# 02-MCU.net
KiCad netlist of a schematic drawn in Altium Designer
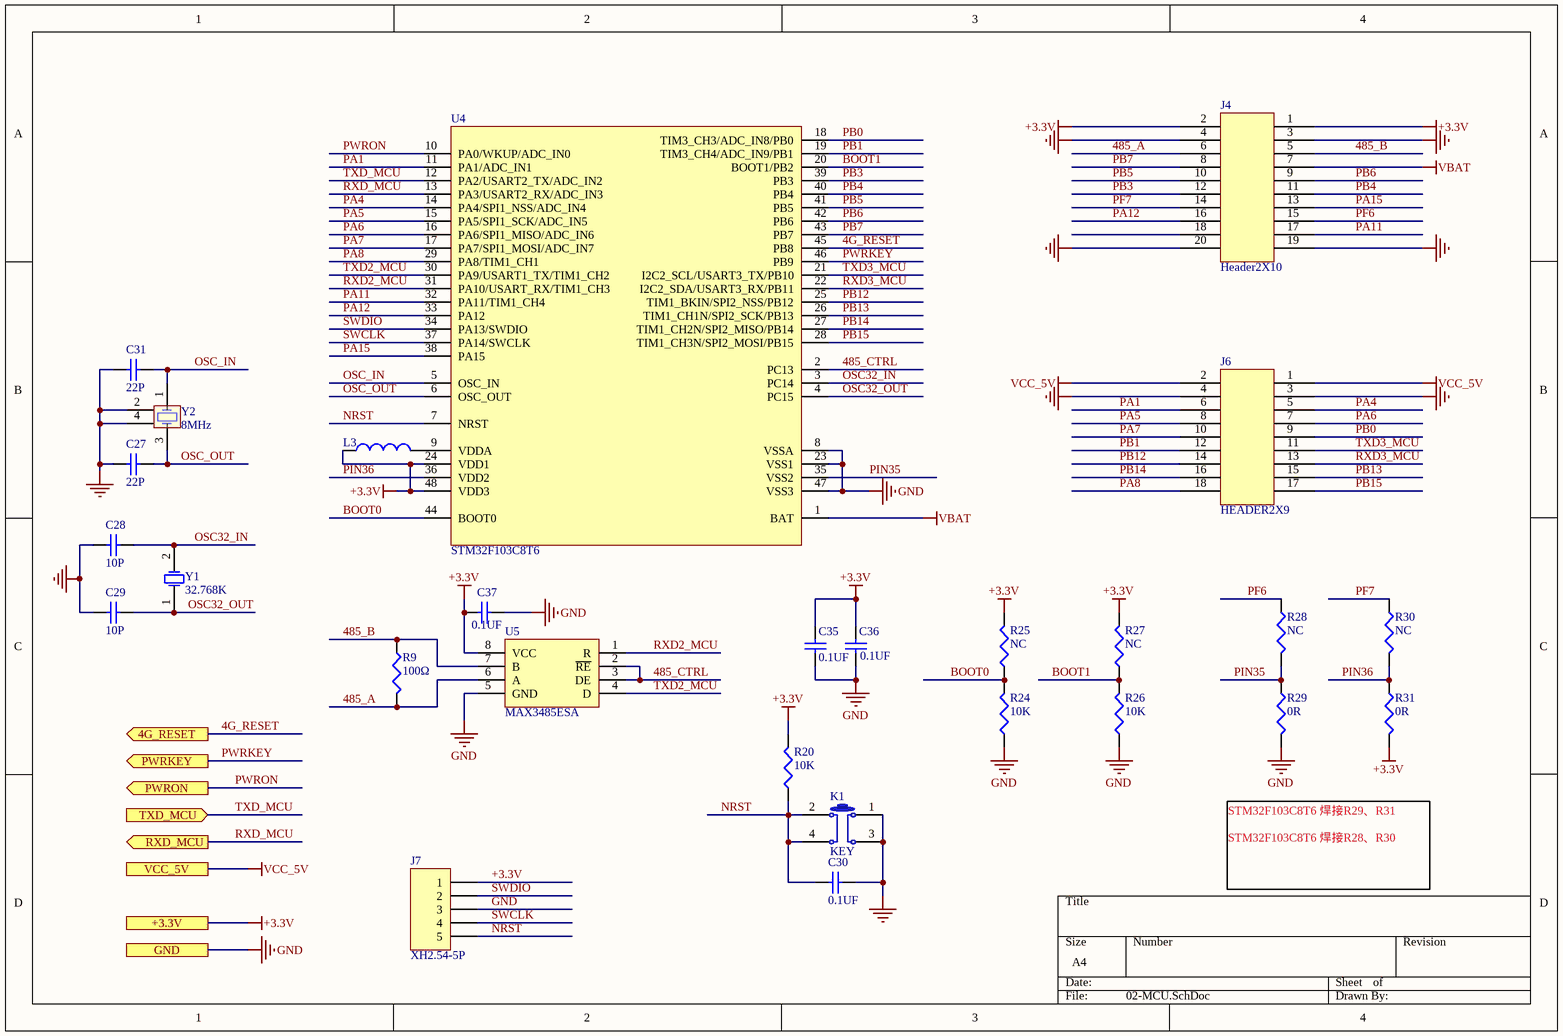
[diagram p0: 02-MCU.SchDoc]

(export (version "E")
  (design (tool "Eeschema 10.0.6"))
  (components
    (comp (ref "C27")
      (value "22P")
      (footprint "0603_C")
      (description "Capacitor")
      (fields (field (name "Comment") "Cap") (field (name "PUBLISHER") "Altium Limited"))
      (libsource (lib "Miscellaneous Devices") (part "Cap"))
    )
    (comp (ref "C28")
      (value "10P")
      (footprint "0603_C")
      (description "Capacitor")
      (fields (field (name "Comment") "Cap") (field (name "PUBLISHER") "Altium Limited"))
      (libsource (lib "Miscellaneous Devices") (part "Cap"))
    )
    (comp (ref "C29")
      (value "10P")
      (footprint "0603_C")
      (description "Capacitor")
      (fields (field (name "Comment") "Cap") (field (name "PUBLISHER") "Altium Limited"))
      (libsource (lib "Miscellaneous Devices") (part "Cap"))
    )
    (comp (ref "C30")
      (value "0.1UF")
      (footprint "0603_C")
      (description "Capacitor")
      (fields (field (name "Comment") "Cap") (field (name "PUBLISHER") "Altium Limited"))
      (libsource (lib "Miscellaneous Devices") (part "Cap"))
    )
    (comp (ref "C31")
      (value "22P")
      (footprint "0603_C")
      (description "Capacitor")
      (fields (field (name "Comment") "Cap") (field (name "PUBLISHER") "Altium Limited"))
      (libsource (lib "Miscellaneous Devices") (part "Cap"))
    )
    (comp (ref "C35")
      (value "0.1UF")
      (footprint "0603_C")
      (description "Capacitor")
      (fields (field (name "Comment") "Cap") (field (name "PUBLISHER") "Altium Limited"))
      (libsource (lib "Miscellaneous Devices") (part "Cap"))
    )
    (comp (ref "C36")
      (value "0.1UF")
      (footprint "0603_C")
      (description "Capacitor")
      (fields (field (name "Comment") "Cap") (field (name "PUBLISHER") "Altium Limited"))
      (libsource (lib "Miscellaneous Devices") (part "Cap"))
    )
    (comp (ref "C37")
      (value "0.1UF")
      (footprint "0603_C")
      (description "Capacitor")
      (fields (field (name "Comment") "Cap") (field (name "PUBLISHER") "Altium Limited"))
      (libsource (lib "Miscellaneous Devices") (part "Cap"))
    )
    (comp (ref "J4")
      (value "Header2X10")
      (footprint "DIP20-2.54-2.54")
      (libsource (lib "MySchlib") (part "Header2X10"))
    )
    (comp (ref "J6")
      (value "HEADER2X9")
      (footprint "DIP18-2.54-2.54")
      (libsource (lib "MySchlib") (part "HEADER2X9"))
    )
    (comp (ref "J7")
      (value "XH2.54-5P")
      (footprint "SIP5")
      (description "Header, 5-Pin, Right Angle")
      (fields (field (name "PUBLISHER") "Altium Limited"))
      (libsource (lib "Miscellaneous Connectors") (part "Header 5H"))
    )
    (comp (ref "K1") (value "KEY") (footprint "KEY_SMD5465") (libsource (lib "Schlib1") (part "KEY")))
    (comp (ref "L3")
      (value "Inductor")
      (footprint "0603_R")
      (fields (field (name "PUBLISHER") "Altium Limited"))
      (libsource (lib "Miscellaneous Devices") (part "Inductor"))
    )
    (comp (ref "R9") (value "100Ω") (footprint "0603_R") (libsource (lib "MySchlib") (part "RES1")))
    (comp (ref "R20")
      (value "10K")
      (footprint "0603_R")
      (description "Resistor")
      (fields (field (name "Comment") "Res3") (field (name "PUBLISHER") "Altium Limited"))
      (libsource (lib "Miscellaneous Devices") (part "Res3"))
    )
    (comp (ref "R24")
      (value "10K")
      (footprint "0603_R")
      (description "Resistor")
      (fields (field (name "Comment") "Res3") (field (name "PUBLISHER") "Altium Limited"))
      (libsource (lib "Miscellaneous Devices") (part "Res3"))
    )
    (comp (ref "R25")
      (value "NC")
      (footprint "0603_R")
      (description "Resistor")
      (fields (field (name "Comment") "Res3") (field (name "PUBLISHER") "Altium Limited"))
      (libsource (lib "Miscellaneous Devices") (part "Res3"))
    )
    (comp (ref "R26")
      (value "10K")
      (footprint "0603_R")
      (description "Resistor")
      (fields (field (name "Comment") "Res3") (field (name "PUBLISHER") "Altium Limited"))
      (libsource (lib "Miscellaneous Devices") (part "Res3"))
    )
    (comp (ref "R27")
      (value "NC")
      (footprint "0603_R")
      (description "Resistor")
      (fields (field (name "Comment") "Res3") (field (name "PUBLISHER") "Altium Limited"))
      (libsource (lib "Miscellaneous Devices") (part "Res3"))
    )
    (comp (ref "R28")
      (value "NC")
      (footprint "0603_R")
      (description "Resistor")
      (fields (field (name "Comment") "Res3") (field (name "PUBLISHER") "Altium Limited"))
      (libsource (lib "Miscellaneous Devices") (part "Res3"))
    )
    (comp (ref "R29")
      (value "0R")
      (footprint "0603_R")
      (description "Resistor")
      (fields (field (name "Comment") "Res3") (field (name "PUBLISHER") "Altium Limited"))
      (libsource (lib "Miscellaneous Devices") (part "Res3"))
    )
    (comp (ref "R30")
      (value "NC")
      (footprint "0603_R")
      (description "Resistor")
      (fields (field (name "Comment") "Res3") (field (name "PUBLISHER") "Altium Limited"))
      (libsource (lib "Miscellaneous Devices") (part "Res3"))
    )
    (comp (ref "R31")
      (value "0R")
      (footprint "0603_R")
      (description "Resistor")
      (fields (field (name "Comment") "Res3") (field (name "PUBLISHER") "Altium Limited"))
      (libsource (lib "Miscellaneous Devices") (part "Res3"))
    )
    (comp (ref "U4")
      (value "STM32F103C8T6")
      (footprint "LQFP48")
      (libsource (lib "MySchlib") (part "STM32F103C8T6"))
    )
    (comp (ref "U5") (value "MAX3485ESA") (footprint "SO8") (libsource (lib "MySchlib") (part "MAX485")))
    (comp (ref "Y1")
      (value "32.768K")
      (footprint "3215")
      (description "Crystal Oscillator")
      (fields (field (name "PUBLISHER") "Altium Limited"))
      (libsource (lib "Miscellaneous Devices") (part "XTAL"))
    )
    (comp (ref "Y2")
      (value "8MHz")
      (footprint "CRY_S3225")
      (description "CRYSTAL_S4_PASSIVE")
      (libsource (lib "EP_MCB_V4.1") (part "CRYSTAL_S4_1"))
    )
  )
  (nets
    (net (code "1") (name "+3.3V") (class "Default")
      (node (ref "C35") (pin "1") (pinfunction "1_1") (pintype "passive"))
      (node (ref "C36") (pin "1") (pinfunction "1_1") (pintype "passive"))
      (node (ref "C37") (pin "1") (pinfunction "1_1") (pintype "passive"))
      (node (ref "J4") (pin "1") (pinfunction "1_1") (pintype "passive"))
      (node (ref "J4") (pin "2") (pinfunction "2_2") (pintype "passive"))
      (node (ref "J7") (pin "1") (pinfunction "1_1") (pintype "passive"))
      (node (ref "L3") (pin "1") (pinfunction "1_1") (pintype "passive"))
      (node (ref "R20") (pin "2") (pinfunction "2_2") (pintype "passive"))
      (node (ref "R25") (pin "2") (pinfunction "2_2") (pintype "passive"))
      (node (ref "R27") (pin "2") (pinfunction "2_2") (pintype "passive"))
      (node (ref "R31") (pin "2") (pinfunction "2_2") (pintype "passive"))
      (node (ref "U4") (pin "24") (pinfunction "VDD1_24") (pintype "passive"))
      (node (ref "U4") (pin "48") (pinfunction "VDD3_48") (pintype "passive"))
      (node (ref "U5") (pin "8") (pinfunction "VCC_8") (pintype "passive"))
    )
    (net (code "2") (name "/4G_RESET") (class "Default")
      (node (ref "U4") (pin "45") (pinfunction "PB8_45") (pintype "passive"))
    )
    (net (code "3") (name "/485_A") (class "Default")
      (node (ref "J4") (pin "6") (pinfunction "6_6") (pintype "passive"))
      (node (ref "R9") (pin "2") (pinfunction "2_2") (pintype "passive"))
      (node (ref "U5") (pin "6") (pinfunction "A_6") (pintype "passive"))
    )
    (net (code "4") (name "/485_B") (class "Default")
      (node (ref "J4") (pin "5") (pinfunction "5_5") (pintype "passive"))
      (node (ref "R9") (pin "1") (pinfunction "1_1") (pintype "passive"))
      (node (ref "U5") (pin "7") (pinfunction "B_7") (pintype "passive"))
    )
    (net (code "5") (name "/485_CTRL") (class "Default")
      (node (ref "U4") (pin "2") (pinfunction "PC13_2") (pintype "passive"))
      (node (ref "U5") (pin "2") (pinfunction "~{RE}_2") (pintype "passive"))
      (node (ref "U5") (pin "3") (pinfunction "DE_3") (pintype "passive"))
    )
    (net (code "6") (name "/BOOT0") (class "Default")
      (node (ref "R24") (pin "2") (pinfunction "2_2") (pintype "passive"))
      (node (ref "R25") (pin "1") (pinfunction "1_1") (pintype "passive"))
      (node (ref "U4") (pin "44") (pinfunction "BOOT0_44") (pintype "passive"))
    )
    (net (code "7") (name "/BOOT1") (class "Default")
      (node (ref "R26") (pin "2") (pinfunction "2_2") (pintype "passive"))
      (node (ref "R27") (pin "1") (pinfunction "1_1") (pintype "passive"))
      (node (ref "U4") (pin "20") (pinfunction "BOOT1/PB2_20") (pintype "passive"))
    )
    (net (code "8") (name "/NRST") (class "Default")
      (node (ref "C30") (pin "2") (pinfunction "2_2") (pintype "passive"))
      (node (ref "J7") (pin "5") (pinfunction "5_5") (pintype "passive"))
      (node (ref "K1") (pin "2") (pinfunction "2_2") (pintype "passive"))
      (node (ref "K1") (pin "4") (pinfunction "4_4") (pintype "passive"))
      (node (ref "R20") (pin "1") (pinfunction "1_1") (pintype "passive"))
      (node (ref "U4") (pin "7") (pinfunction "NRST_7") (pintype "passive"))
    )
    (net (code "9") (name "/OSC32_IN") (class "Default")
      (node (ref "C28") (pin "1") (pinfunction "1_1") (pintype "passive"))
      (node (ref "U4") (pin "3") (pinfunction "PC14_3") (pintype "passive"))
      (node (ref "Y1") (pin "2") (pinfunction "OSC2_2") (pintype "passive"))
    )
    (net (code "10") (name "/OSC32_OUT") (class "Default")
      (node (ref "C29") (pin "1") (pinfunction "1_1") (pintype "passive"))
      (node (ref "U4") (pin "4") (pinfunction "PC15_4") (pintype "passive"))
      (node (ref "Y1") (pin "1") (pinfunction "OSC1_1") (pintype "passive"))
    )
    (net (code "11") (name "/OSC_IN") (class "Default")
      (node (ref "C31") (pin "1") (pinfunction "1_1") (pintype "passive"))
      (node (ref "U4") (pin "5") (pinfunction "OSC_IN_5") (pintype "passive"))
      (node (ref "Y2") (pin "1") (pinfunction "1_1") (pintype "passive"))
    )
    (net (code "12") (name "/OSC_OUT") (class "Default")
      (node (ref "C27") (pin "1") (pinfunction "1_1") (pintype "passive"))
      (node (ref "U4") (pin "6") (pinfunction "OSC_OUT_6") (pintype "passive"))
      (node (ref "Y2") (pin "3") (pinfunction "3_3") (pintype "passive"))
    )
    (net (code "13") (name "/PA1") (class "Default")
      (node (ref "J6") (pin "6") (pinfunction "6_6") (pintype "passive"))
      (node (ref "U4") (pin "11") (pinfunction "PA1/ADC_IN1_11") (pintype "passive"))
    )
    (net (code "14") (name "/PA4") (class "Default")
      (node (ref "J6") (pin "5") (pinfunction "5_5") (pintype "passive"))
      (node (ref "U4") (pin "14") (pinfunction "PA4/SPI1_NSS/ADC_IN4_14") (pintype "passive"))
    )
    (net (code "15") (name "/PA5") (class "Default")
      (node (ref "J6") (pin "8") (pinfunction "8_8") (pintype "passive"))
      (node (ref "U4") (pin "15") (pinfunction "PA5/SPI1_SCK/ADC_IN5_15") (pintype "passive"))
    )
    (net (code "16") (name "/PA6") (class "Default")
      (node (ref "J6") (pin "7") (pinfunction "7_7") (pintype "passive"))
      (node (ref "U4") (pin "16") (pinfunction "PA6/SPI1_MISO/ADC_IN6_16") (pintype "passive"))
    )
    (net (code "17") (name "/PA7") (class "Default")
      (node (ref "J6") (pin "10") (pinfunction "10_10") (pintype "passive"))
      (node (ref "U4") (pin "17") (pinfunction "PA7/SPI1_MOSI/ADC_IN7_17") (pintype "passive"))
    )
    (net (code "18") (name "/PA8") (class "Default")
      (node (ref "J6") (pin "18") (pinfunction "18_18") (pintype "passive"))
      (node (ref "U4") (pin "29") (pinfunction "PA8/TIM1_CH1_29") (pintype "passive"))
    )
    (net (code "19") (name "/PA11") (class "Default")
      (node (ref "J4") (pin "17") (pinfunction "17_17") (pintype "passive"))
      (node (ref "U4") (pin "32") (pinfunction "PA11/TIM1_CH4_32") (pintype "passive"))
    )
    (net (code "20") (name "/PA12") (class "Default")
      (node (ref "J4") (pin "16") (pinfunction "16_16") (pintype "passive"))
      (node (ref "U4") (pin "33") (pinfunction "PA12_33") (pintype "passive"))
    )
    (net (code "21") (name "/PA15") (class "Default")
      (node (ref "J4") (pin "13") (pinfunction "13_13") (pintype "passive"))
      (node (ref "U4") (pin "38") (pinfunction "PA15_38") (pintype "passive"))
    )
    (net (code "22") (name "/PB0") (class "Default")
      (node (ref "J6") (pin "9") (pinfunction "9_9") (pintype "passive"))
      (node (ref "U4") (pin "18") (pinfunction "TIM3_CH3/ADC_IN8/PB0_18") (pintype "passive"))
    )
    (net (code "23") (name "/PB1") (class "Default")
      (node (ref "J6") (pin "12") (pinfunction "12_12") (pintype "passive"))
      (node (ref "U4") (pin "19") (pinfunction "TIM3_CH4/ADC_IN9/PB1_19") (pintype "passive"))
    )
    (net (code "24") (name "/PB3") (class "Default")
      (node (ref "J4") (pin "12") (pinfunction "12_12") (pintype "passive"))
      (node (ref "U4") (pin "39") (pinfunction "PB3_39") (pintype "passive"))
    )
    (net (code "25") (name "/PB4") (class "Default")
      (node (ref "J4") (pin "11") (pinfunction "11_11") (pintype "passive"))
      (node (ref "U4") (pin "40") (pinfunction "PB4_40") (pintype "passive"))
    )
    (net (code "26") (name "/PB5") (class "Default")
      (node (ref "J4") (pin "10") (pinfunction "10_10") (pintype "passive"))
      (node (ref "U4") (pin "41") (pinfunction "PB5_41") (pintype "passive"))
    )
    (net (code "27") (name "/PB6") (class "Default")
      (node (ref "J4") (pin "9") (pinfunction "9_9") (pintype "passive"))
      (node (ref "U4") (pin "42") (pinfunction "PB6_42") (pintype "passive"))
    )
    (net (code "28") (name "/PB7") (class "Default")
      (node (ref "J4") (pin "8") (pinfunction "8_8") (pintype "passive"))
      (node (ref "U4") (pin "43") (pinfunction "PB7_43") (pintype "passive"))
    )
    (net (code "29") (name "/PB12") (class "Default")
      (node (ref "J6") (pin "14") (pinfunction "14_14") (pintype "passive"))
      (node (ref "U4") (pin "25") (pinfunction "TIM1_BKIN/SPI2_NSS/PB12_25") (pintype "passive"))
    )
    (net (code "30") (name "/PB13") (class "Default")
      (node (ref "J6") (pin "15") (pinfunction "15_15") (pintype "passive"))
      (node (ref "U4") (pin "26") (pinfunction "TIM1_CH1N/SPI2_SCK/PB13_26") (pintype "passive"))
    )
    (net (code "31") (name "/PB14") (class "Default")
      (node (ref "J6") (pin "16") (pinfunction "16_16") (pintype "passive"))
      (node (ref "U4") (pin "27") (pinfunction "TIM1_CH2N/SPI2_MISO/PB14_27") (pintype "passive"))
    )
    (net (code "32") (name "/PB15") (class "Default")
      (node (ref "J6") (pin "17") (pinfunction "17_17") (pintype "passive"))
      (node (ref "U4") (pin "28") (pinfunction "TIM1_CH3N/SPI2_MOSI/PB15_28") (pintype "passive"))
    )
    (net (code "33") (name "/PF6") (class "Default")
      (node (ref "J4") (pin "15") (pinfunction "15_15") (pintype "passive"))
      (node (ref "R28") (pin "1") (pinfunction "1_1") (pintype "passive"))
    )
    (net (code "34") (name "/PF7") (class "Default")
      (node (ref "J4") (pin "14") (pinfunction "14_14") (pintype "passive"))
      (node (ref "R30") (pin "1") (pinfunction "1_1") (pintype "passive"))
    )
    (net (code "35") (name "/PIN35") (class "Default")
      (node (ref "R28") (pin "2") (pinfunction "2_2") (pintype "passive"))
      (node (ref "R29") (pin "1") (pinfunction "1_1") (pintype "passive"))
      (node (ref "U4") (pin "35") (pinfunction "VSS2_35") (pintype "passive"))
    )
    (net (code "36") (name "/PIN36") (class "Default")
      (node (ref "R30") (pin "2") (pinfunction "2_2") (pintype "passive"))
      (node (ref "R31") (pin "1") (pinfunction "1_1") (pintype "passive"))
      (node (ref "U4") (pin "36") (pinfunction "VDD2_36") (pintype "passive"))
    )
    (net (code "37") (name "/PWRKEY") (class "Default")
      (node (ref "U4") (pin "46") (pinfunction "PB9_46") (pintype "passive"))
    )
    (net (code "38") (name "/PWRON") (class "Default")
      (node (ref "U4") (pin "10") (pinfunction "PA0/WKUP/ADC_IN0_10") (pintype "passive"))
    )
    (net (code "39") (name "/RXD2_MCU") (class "Default")
      (node (ref "U4") (pin "31") (pinfunction "PA10/USART_RX/TIM1_CH3_31") (pintype "passive"))
      (node (ref "U5") (pin "1") (pinfunction "R_1") (pintype "passive"))
    )
    (net (code "40") (name "/RXD3_MCU") (class "Default")
      (node (ref "J6") (pin "13") (pinfunction "13_13") (pintype "passive"))
      (node (ref "U4") (pin "22") (pinfunction "I2C2_SDA/USART3_RX/PB11_22") (pintype "passive"))
    )
    (net (code "41") (name "/RXD_MCU") (class "Default")
      (node (ref "U4") (pin "13") (pinfunction "PA3/USART2_RX/ADC_IN3_13") (pintype "passive"))
    )
    (net (code "42") (name "/SWCLK") (class "Default")
      (node (ref "J7") (pin "4") (pinfunction "4_4") (pintype "passive"))
      (node (ref "U4") (pin "37") (pinfunction "PA14/SWCLK_37") (pintype "passive"))
    )
    (net (code "43") (name "/SWDIO") (class "Default")
      (node (ref "J7") (pin "2") (pinfunction "2_2") (pintype "passive"))
      (node (ref "U4") (pin "34") (pinfunction "PA13/SWDIO_34") (pintype "passive"))
    )
    (net (code "44") (name "/TXD2_MCU") (class "Default")
      (node (ref "U4") (pin "30") (pinfunction "PA9/USART1_TX/TIM1_CH2_30") (pintype "passive"))
      (node (ref "U5") (pin "4") (pinfunction "D_4") (pintype "passive"))
    )
    (net (code "45") (name "/TXD3_MCU") (class "Default")
      (node (ref "J6") (pin "11") (pinfunction "11_11") (pintype "passive"))
      (node (ref "U4") (pin "21") (pinfunction "I2C2_SCL/USART3_TX/PB10_21") (pintype "passive"))
    )
    (net (code "46") (name "/TXD_MCU") (class "Default")
      (node (ref "U4") (pin "12") (pinfunction "PA2/USART2_TX/ADC_IN2_12") (pintype "passive"))
    )
    (net (code "47") (name "GND") (class "Default")
      (node (ref "C27") (pin "2") (pinfunction "2_2") (pintype "passive"))
      (node (ref "C28") (pin "2") (pinfunction "2_2") (pintype "passive"))
      (node (ref "C29") (pin "2") (pinfunction "2_2") (pintype "passive"))
      (node (ref "C30") (pin "1") (pinfunction "1_1") (pintype "passive"))
      (node (ref "C31") (pin "2") (pinfunction "2_2") (pintype "passive"))
      (node (ref "C35") (pin "2") (pinfunction "2_2") (pintype "passive"))
      (node (ref "C36") (pin "2") (pinfunction "2_2") (pintype "passive"))
      (node (ref "C37") (pin "2") (pinfunction "2_2") (pintype "passive"))
      (node (ref "J4") (pin "19") (pinfunction "19_19") (pintype "passive"))
      (node (ref "J4") (pin "20") (pinfunction "20_20") (pintype "passive"))
      (node (ref "J4") (pin "3") (pinfunction "3_3") (pintype "passive"))
      (node (ref "J4") (pin "4") (pinfunction "4_4") (pintype "passive"))
      (node (ref "J6") (pin "3") (pinfunction "3_3") (pintype "passive"))
      (node (ref "J6") (pin "4") (pinfunction "4_4") (pintype "passive"))
      (node (ref "J7") (pin "3") (pinfunction "3_3") (pintype "passive"))
      (node (ref "K1") (pin "1") (pinfunction "1_1") (pintype "passive"))
      (node (ref "K1") (pin "3") (pinfunction "3_3") (pintype "passive"))
      (node (ref "R24") (pin "1") (pinfunction "1_1") (pintype "passive"))
      (node (ref "R26") (pin "1") (pinfunction "1_1") (pintype "passive"))
      (node (ref "R29") (pin "2") (pinfunction "2_2") (pintype "passive"))
      (node (ref "U4") (pin "23") (pinfunction "VSS1_23") (pintype "passive"))
      (node (ref "U4") (pin "47") (pinfunction "VSS3_47") (pintype "passive"))
      (node (ref "U4") (pin "8") (pinfunction "VSSA_8") (pintype "passive"))
      (node (ref "U5") (pin "5") (pinfunction "GND_5") (pintype "passive"))
      (node (ref "Y2") (pin "2") (pinfunction "2_2") (pintype "passive"))
      (node (ref "Y2") (pin "4") (pinfunction "4_4") (pintype "passive"))
    )
    (net (code "48") (name "Net-(U4-VDDA)") (class "Default")
      (node (ref "L3") (pin "2") (pinfunction "2_2") (pintype "passive"))
      (node (ref "U4") (pin "9") (pinfunction "VDDA_9") (pintype "passive"))
    )
    (net (code "49") (name "VBAT") (class "Default")
      (node (ref "J4") (pin "7") (pinfunction "7_7") (pintype "passive"))
      (node (ref "U4") (pin "1") (pinfunction "BAT_1") (pintype "passive"))
    )
    (net (code "50") (name "VCC_5V") (class "Default")
      (node (ref "J6") (pin "1") (pinfunction "1_1") (pintype "passive"))
      (node (ref "J6") (pin "2") (pinfunction "2_2") (pintype "passive"))
    )
    (net (code "51") (name "unconnected-(J4-Pad18)") (class "Default")
      (node (ref "J4") (pin "18") (pinfunction "18_18") (pintype "passive"))
    )
  )
)
